# Inverter.net
KiCad netlist of a schematic drawn in Altium Designer
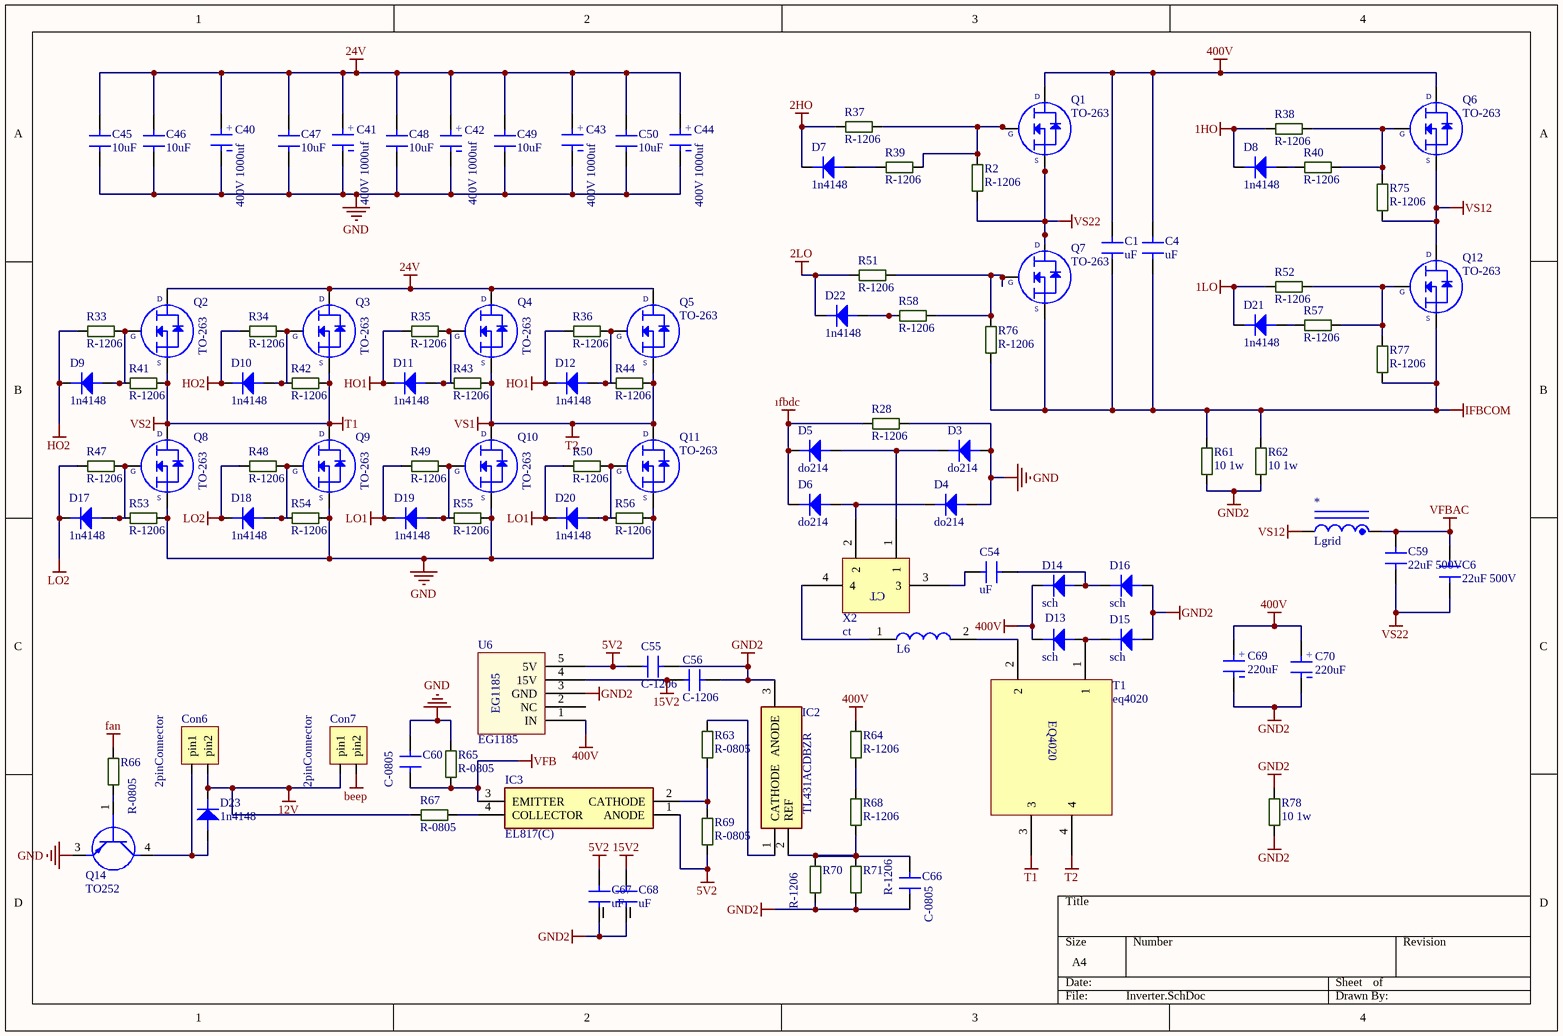
[diagram p0: Inverter.SchDoc]

(export (version "E")
  (design (tool "Eeschema 10.0.6"))
  (components
    (comp (ref "*") (value "Lgrid") (footprint "Lgrid") (libsource (lib "Schlib1") (part "Lgrid")))
    (comp (ref "C1") (value "uF") (footprint "680nF bulk") (libsource (lib "Schlib1") (part "680")))
    (comp (ref "C4") (value "uF") (footprint "680nF bulk") (libsource (lib "Schlib1") (part "680")))
    (comp (ref "C6")
      (value "22uF 500V")
      (footprint "CAP.POL 22UF 500VDC - duplicate")
      (libsource (lib "Schlib1") (part "CAP.POL 22UF 500VDC"))
    )
    (comp (ref "C40")
      (value "400V 1000uf")
      (footprint "CAP_EEETC1C331V")
      (fields
        (field (name "MANUFACTURER") "Nichicon")
        (field (name "MANUFACTURER PART NUMBER") "LKS1J472MESZ")
        (field (name "TOLERANCE") "20%")
      )
      (libsource (lib "Schlib1") (part "Aluminum Electrolytic Capacitors"))
    )
    (comp (ref "C41")
      (value "400V 1000uf")
      (footprint "CAP_EEETC1C331V")
      (fields
        (field (name "MANUFACTURER") "Nichicon")
        (field (name "MANUFACTURER PART NUMBER") "LKS1J472MESZ")
        (field (name "TOLERANCE") "20%")
      )
      (libsource (lib "Schlib1") (part "Aluminum Electrolytic Capacitors"))
    )
    (comp (ref "C42")
      (value "400V 1000uf")
      (footprint "CAP_EEETC1C331V")
      (fields
        (field (name "MANUFACTURER") "Nichicon")
        (field (name "MANUFACTURER PART NUMBER") "LKS1J472MESZ")
        (field (name "TOLERANCE") "20%")
      )
      (libsource (lib "Schlib1") (part "Aluminum Electrolytic Capacitors"))
    )
    (comp (ref "C43")
      (value "400V 1000uf")
      (footprint "CAP_EEETC1C331V")
      (fields
        (field (name "MANUFACTURER") "Nichicon")
        (field (name "MANUFACTURER PART NUMBER") "LKS1J472MESZ")
        (field (name "TOLERANCE") "20%")
      )
      (libsource (lib "Schlib1") (part "Aluminum Electrolytic Capacitors"))
    )
    (comp (ref "C44")
      (value "400V 1000uf")
      (footprint "CAP_EEETC1C331V")
      (fields
        (field (name "MANUFACTURER") "Nichicon")
        (field (name "MANUFACTURER PART NUMBER") "LKS1J472MESZ")
        (field (name "TOLERANCE") "20%")
      )
      (libsource (lib "Schlib1") (part "Aluminum Electrolytic Capacitors"))
    )
    (comp (ref "C45")
      (value "10uF")
      (footprint "C-2220R")
      (description "2220")
      (fields (field (name "ÖZDISAN PART NUMBER") " CL31B475KBHNNNE") (field (name "MANUFACTURER") "SAMSUNG"))
      (libsource (lib "Schlib1") (part "Cap2220"))
    )
    (comp (ref "C46")
      (value "10uF")
      (footprint "C-2220R")
      (description "2220")
      (fields (field (name "ÖZDISAN PART NUMBER") " CL31B475KBHNNNE") (field (name "MANUFACTURER") "SAMSUNG"))
      (libsource (lib "Schlib1") (part "Cap2220"))
    )
    (comp (ref "C47")
      (value "10uF")
      (footprint "C-2220R")
      (description "2220")
      (fields (field (name "ÖZDISAN PART NUMBER") " CL31B475KBHNNNE") (field (name "MANUFACTURER") "SAMSUNG"))
      (libsource (lib "Schlib1") (part "Cap2220"))
    )
    (comp (ref "C48")
      (value "10uF")
      (footprint "C-2220R")
      (description "2220")
      (fields (field (name "ÖZDISAN PART NUMBER") " CL31B475KBHNNNE") (field (name "MANUFACTURER") "SAMSUNG"))
      (libsource (lib "Schlib1") (part "Cap2220"))
    )
    (comp (ref "C49")
      (value "10uF")
      (footprint "C-2220R")
      (description "2220")
      (fields (field (name "ÖZDISAN PART NUMBER") " CL31B475KBHNNNE") (field (name "MANUFACTURER") "SAMSUNG"))
      (libsource (lib "Schlib1") (part "Cap2220"))
    )
    (comp (ref "C50")
      (value "10uF")
      (footprint "C-2220R")
      (description "2220")
      (fields (field (name "ÖZDISAN PART NUMBER") " CL31B475KBHNNNE") (field (name "MANUFACTURER") "SAMSUNG"))
      (libsource (lib "Schlib1") (part "Cap2220"))
    )
    (comp (ref "C54") (value "uF") (footprint "680nF bulk") (libsource (lib "Schlib1") (part "680")))
    (comp (ref "C55") (value "C-1206") (footprint "C-1206W") (libsource (lib "Schlib1") (part "C-1206")))
    (comp (ref "C56") (value "C-1206") (footprint "C-1206W") (libsource (lib "Schlib1") (part "C-1206")))
    (comp (ref "C59")
      (value "22uF 500V")
      (footprint "CAP.POL 22UF 500VDC - duplicate")
      (libsource (lib "Schlib1") (part "CAP.POL 22UF 500VDC"))
    )
    (comp (ref "C60") (value "C-0805") (footprint "C-0805W") (libsource (lib "Schlib1") (part "C-0805")))
    (comp (ref "C66") (value "C-0805") (footprint "C-0805W") (libsource (lib "Schlib1") (part "C-0805")))
    (comp (ref "C67") (value "uF") (footprint "CapSmdElc") (libsource (lib "Schlib1") (part "CAPSMDELC")))
    (comp (ref "C68") (value "uF") (footprint "CapSmdElc") (libsource (lib "Schlib1") (part "CAPSMDELC")))
    (comp (ref "C69")
      (value "220uF")
      (footprint "Koshin")
      (libsource (lib "Schlib1") (part "CAP.EL.220uF 500V"))
    )
    (comp (ref "C70")
      (value "220uF")
      (footprint "Koshin")
      (libsource (lib "Schlib1") (part "CAP.EL.220uF 500V"))
    )
    (comp (ref "Con6")
      (value "2pinConnector")
      (footprint "2pinCon")
      (libsource (lib "Schlib1") (part "2pinConnector"))
    )
    (comp (ref "Con7")
      (value "2pinConnector")
      (footprint "2pinCon")
      (libsource (lib "Schlib1") (part "2pinConnector"))
    )
    (comp (ref "D3")
      (value "do214")
      (footprint "DO-214AC")
      (description "DIODE FAST SWITCHING Single 150mA 75V SMT SOD323")
      (libsource (lib "Schlib1") (part "do214"))
    )
    (comp (ref "D4")
      (value "do214")
      (footprint "DO-214AC")
      (description "DIODE FAST SWITCHING Single 150mA 75V SMT SOD323")
      (libsource (lib "Schlib1") (part "do214"))
    )
    (comp (ref "D5")
      (value "do214")
      (footprint "DO-214AC")
      (description "DIODE FAST SWITCHING Single 150mA 75V SMT SOD323")
      (libsource (lib "Schlib1") (part "do214"))
    )
    (comp (ref "D6")
      (value "do214")
      (footprint "DO-214AC")
      (description "DIODE FAST SWITCHING Single 150mA 75V SMT SOD323")
      (libsource (lib "Schlib1") (part "do214"))
    )
    (comp (ref "D7")
      (value "1n4148")
      (footprint "SOD123")
      (description "Diode Small Signal Switching 100V 0.15A 2-Pin SOD-123 T/R")
      (fields
        (field (name "MANUFACTURER") "Vishay")
        (field (name "MANUFACTURER PART NUMBER") "1N4148W-E3-18")
      )
      (libsource (lib "Schlib1") (part "1N4148W-E3-18"))
    )
    (comp (ref "D8")
      (value "1n4148")
      (footprint "SOD123")
      (description "Diode Small Signal Switching 100V 0.15A 2-Pin SOD-123 T/R")
      (fields
        (field (name "MANUFACTURER") "Vishay")
        (field (name "MANUFACTURER PART NUMBER") "1N4148W-E3-18")
      )
      (libsource (lib "Schlib1") (part "1N4148W-E3-18"))
    )
    (comp (ref "D9")
      (value "1n4148")
      (footprint "SOD123")
      (description "Diode Small Signal Switching 100V 0.15A 2-Pin SOD-123 T/R")
      (fields
        (field (name "MANUFACTURER") "Vishay")
        (field (name "MANUFACTURER PART NUMBER") "1N4148W-E3-18")
      )
      (libsource (lib "Schlib1") (part "1N4148W-E3-18"))
    )
    (comp (ref "D10")
      (value "1n4148")
      (footprint "SOD123")
      (description "Diode Small Signal Switching 100V 0.15A 2-Pin SOD-123 T/R")
      (fields
        (field (name "MANUFACTURER") "Vishay")
        (field (name "MANUFACTURER PART NUMBER") "1N4148W-E3-18")
      )
      (libsource (lib "Schlib1") (part "1N4148W-E3-18"))
    )
    (comp (ref "D11")
      (value "1n4148")
      (footprint "SOD123")
      (description "Diode Small Signal Switching 100V 0.15A 2-Pin SOD-123 T/R")
      (fields
        (field (name "MANUFACTURER") "Vishay")
        (field (name "MANUFACTURER PART NUMBER") "1N4148W-E3-18")
      )
      (libsource (lib "Schlib1") (part "1N4148W-E3-18"))
    )
    (comp (ref "D12")
      (value "1n4148")
      (footprint "SOD123")
      (description "Diode Small Signal Switching 100V 0.15A 2-Pin SOD-123 T/R")
      (fields
        (field (name "MANUFACTURER") "Vishay")
        (field (name "MANUFACTURER PART NUMBER") "1N4148W-E3-18")
      )
      (libsource (lib "Schlib1") (part "1N4148W-E3-18"))
    )
    (comp (ref "D13")
      (value "sch")
      (footprint "DPAK_TO263 - sch")
      (description "DIODE FAST SWITCHING Single 150mA 75V SMT SOD323")
      (libsource (lib "Schlib1") (part "sch"))
    )
    (comp (ref "D14")
      (value "sch")
      (footprint "DPAK_TO263 - sch")
      (description "DIODE FAST SWITCHING Single 150mA 75V SMT SOD323")
      (libsource (lib "Schlib1") (part "sch"))
    )
    (comp (ref "D15")
      (value "sch")
      (footprint "DPAK_TO263 - sch")
      (description "DIODE FAST SWITCHING Single 150mA 75V SMT SOD323")
      (libsource (lib "Schlib1") (part "sch"))
    )
    (comp (ref "D16")
      (value "sch")
      (footprint "DPAK_TO263 - sch")
      (description "DIODE FAST SWITCHING Single 150mA 75V SMT SOD323")
      (libsource (lib "Schlib1") (part "sch"))
    )
    (comp (ref "D17")
      (value "1n4148")
      (footprint "SOD123")
      (description "Diode Small Signal Switching 100V 0.15A 2-Pin SOD-123 T/R")
      (fields
        (field (name "MANUFACTURER") "Vishay")
        (field (name "MANUFACTURER PART NUMBER") "1N4148W-E3-18")
      )
      (libsource (lib "Schlib1") (part "1N4148W-E3-18"))
    )
    (comp (ref "D18")
      (value "1n4148")
      (footprint "SOD123")
      (description "Diode Small Signal Switching 100V 0.15A 2-Pin SOD-123 T/R")
      (fields
        (field (name "MANUFACTURER") "Vishay")
        (field (name "MANUFACTURER PART NUMBER") "1N4148W-E3-18")
      )
      (libsource (lib "Schlib1") (part "1N4148W-E3-18"))
    )
    (comp (ref "D19")
      (value "1n4148")
      (footprint "SOD123")
      (description "Diode Small Signal Switching 100V 0.15A 2-Pin SOD-123 T/R")
      (fields
        (field (name "MANUFACTURER") "Vishay")
        (field (name "MANUFACTURER PART NUMBER") "1N4148W-E3-18")
      )
      (libsource (lib "Schlib1") (part "1N4148W-E3-18"))
    )
    (comp (ref "D20")
      (value "1n4148")
      (footprint "SOD123")
      (description "Diode Small Signal Switching 100V 0.15A 2-Pin SOD-123 T/R")
      (fields
        (field (name "MANUFACTURER") "Vishay")
        (field (name "MANUFACTURER PART NUMBER") "1N4148W-E3-18")
      )
      (libsource (lib "Schlib1") (part "1N4148W-E3-18"))
    )
    (comp (ref "D21")
      (value "1n4148")
      (footprint "SOD123")
      (description "Diode Small Signal Switching 100V 0.15A 2-Pin SOD-123 T/R")
      (fields
        (field (name "MANUFACTURER") "Vishay")
        (field (name "MANUFACTURER PART NUMBER") "1N4148W-E3-18")
      )
      (libsource (lib "Schlib1") (part "1N4148W-E3-18"))
    )
    (comp (ref "D22")
      (value "1n4148")
      (footprint "SOD123")
      (description "Diode Small Signal Switching 100V 0.15A 2-Pin SOD-123 T/R")
      (fields
        (field (name "MANUFACTURER") "Vishay")
        (field (name "MANUFACTURER PART NUMBER") "1N4148W-E3-18")
      )
      (libsource (lib "Schlib1") (part "1N4148W-E3-18"))
    )
    (comp (ref "D23")
      (value "1n4148")
      (footprint "SOD123")
      (description "Diode Small Signal Switching 100V 0.15A 2-Pin SOD-123 T/R")
      (fields
        (field (name "MANUFACTURER") "Vishay")
        (field (name "MANUFACTURER PART NUMBER") "1N4148W-E3-18")
      )
      (libsource (lib "Schlib1") (part "1N4148W-E3-18"))
    )
    (comp (ref "IC2")
      (value "TL431ACDBZR")
      (footprint "SamacSys:SOT95P237X112-3N")
      (description "Integrated Circuit")
      (fields (field (name "MOUSER PART NUMBER") "595-TL431ACDBZR"))
      (libsource (lib "*") (part "TL431ACDBZR"))
    )
    (comp (ref "IC3")
      (value "EL817(C)")
      (footprint "DIP762W60P254L458H480Q4N")
      (description "Integrated Circuit")
      (fields (field (name "MOUSER PART NUMBER") "638-EL817C"))
      (libsource (lib "Schlib1") (part "EL817(C)"))
    )
    (comp (ref "L6")
      (value "inducter_SMPI06050")
      (footprint "inductor")
      (libsource (lib "Schlib1") (part "inducter_SMPI06050"))
    )
    (comp (ref "Q1") (value "TO-263") (footprint "DPAK_TO263") (libsource (lib "Schlib1") (part "TO-263_1")))
    (comp (ref "Q2") (value "TO-263") (footprint "DPAK_TO263") (libsource (lib "Schlib1") (part "TO-263_1")))
    (comp (ref "Q3") (value "TO-263") (footprint "DPAK_TO263") (libsource (lib "Schlib1") (part "TO-263_1")))
    (comp (ref "Q4") (value "TO-263") (footprint "DPAK_TO263") (libsource (lib "Schlib1") (part "TO-263_1")))
    (comp (ref "Q5") (value "TO-263") (footprint "DPAK_TO263") (libsource (lib "Schlib1") (part "TO-263_1")))
    (comp (ref "Q6") (value "TO-263") (footprint "DPAK_TO263") (libsource (lib "Schlib1") (part "TO-263_1")))
    (comp (ref "Q7") (value "TO-263") (footprint "DPAK_TO263") (libsource (lib "Schlib1") (part "TO-263_1")))
    (comp (ref "Q8") (value "TO-263") (footprint "DPAK_TO263") (libsource (lib "Schlib1") (part "TO-263_1")))
    (comp (ref "Q9") (value "TO-263") (footprint "DPAK_TO263") (libsource (lib "Schlib1") (part "TO-263_1")))
    (comp (ref "Q10") (value "TO-263") (footprint "DPAK_TO263") (libsource (lib "Schlib1") (part "TO-263_1")))
    (comp (ref "Q11") (value "TO-263") (footprint "DPAK_TO263") (libsource (lib "Schlib1") (part "TO-263_1")))
    (comp (ref "Q12") (value "TO-263") (footprint "DPAK_TO263") (libsource (lib "Schlib1") (part "TO-263_1")))
    (comp (ref "Q14") (value "TO252") (footprint "D-PAK_TO252AA") (libsource (lib "Schlib1") (part "TO252")))
    (comp (ref "R2") (value "R-1206") (footprint "R-1206W") (libsource (lib "Schlib1") (part "R-1206")))
    (comp (ref "R28") (value "R-1206") (footprint "R-1206W") (libsource (lib "Schlib1") (part "R-1206")))
    (comp (ref "R33") (value "R-1206") (footprint "R-1206W") (libsource (lib "Schlib1") (part "R-1206")))
    (comp (ref "R34") (value "R-1206") (footprint "R-1206W") (libsource (lib "Schlib1") (part "R-1206")))
    (comp (ref "R35") (value "R-1206") (footprint "R-1206W") (libsource (lib "Schlib1") (part "R-1206")))
    (comp (ref "R36") (value "R-1206") (footprint "R-1206W") (libsource (lib "Schlib1") (part "R-1206")))
    (comp (ref "R37") (value "R-1206") (footprint "R-1206W") (libsource (lib "Schlib1") (part "R-1206")))
    (comp (ref "R38") (value "R-1206") (footprint "R-1206W") (libsource (lib "Schlib1") (part "R-1206")))
    (comp (ref "R39") (value "R-1206") (footprint "R-1206W") (libsource (lib "Schlib1") (part "R-1206")))
    (comp (ref "R40") (value "R-1206") (footprint "R-1206W") (libsource (lib "Schlib1") (part "R-1206")))
    (comp (ref "R41") (value "R-1206") (footprint "R-1206W") (libsource (lib "Schlib1") (part "R-1206")))
    (comp (ref "R42") (value "R-1206") (footprint "R-1206W") (libsource (lib "Schlib1") (part "R-1206")))
    (comp (ref "R43") (value "R-1206") (footprint "R-1206W") (libsource (lib "Schlib1") (part "R-1206")))
    (comp (ref "R44") (value "R-1206") (footprint "R-1206W") (libsource (lib "Schlib1") (part "R-1206")))
    (comp (ref "R47") (value "R-1206") (footprint "R-1206W") (libsource (lib "Schlib1") (part "R-1206")))
    (comp (ref "R48") (value "R-1206") (footprint "R-1206W") (libsource (lib "Schlib1") (part "R-1206")))
    (comp (ref "R49") (value "R-1206") (footprint "R-1206W") (libsource (lib "Schlib1") (part "R-1206")))
    (comp (ref "R50") (value "R-1206") (footprint "R-1206W") (libsource (lib "Schlib1") (part "R-1206")))
    (comp (ref "R51") (value "R-1206") (footprint "R-1206W") (libsource (lib "Schlib1") (part "R-1206")))
    (comp (ref "R52") (value "R-1206") (footprint "R-1206W") (libsource (lib "Schlib1") (part "R-1206")))
    (comp (ref "R53") (value "R-1206") (footprint "R-1206W") (libsource (lib "Schlib1") (part "R-1206")))
    (comp (ref "R54") (value "R-1206") (footprint "R-1206W") (libsource (lib "Schlib1") (part "R-1206")))
    (comp (ref "R55") (value "R-1206") (footprint "R-1206W") (libsource (lib "Schlib1") (part "R-1206")))
    (comp (ref "R56") (value "R-1206") (footprint "R-1206W") (libsource (lib "Schlib1") (part "R-1206")))
    (comp (ref "R57") (value "R-1206") (footprint "R-1206W") (libsource (lib "Schlib1") (part "R-1206")))
    (comp (ref "R58") (value "R-1206") (footprint "R-1206W") (libsource (lib "Schlib1") (part "R-1206")))
    (comp (ref "R61") (value "10 1w") (footprint "R-2512W") (libsource (lib "Schlib1") (part "R-2512")))
    (comp (ref "R62") (value "10 1w") (footprint "R-2512W") (libsource (lib "Schlib1") (part "R-2512")))
    (comp (ref "R63") (value "R-0805") (footprint "R-0805W") (libsource (lib "Schlib1") (part "R-0805")))
    (comp (ref "R64") (value "R-1206") (footprint "R-1206W") (libsource (lib "Schlib1") (part "R-1206")))
    (comp (ref "R65") (value "R-0805") (footprint "R-0805W") (libsource (lib "Schlib1") (part "R-0805")))
    (comp (ref "R66") (value "R-0805") (footprint "R-0805W") (libsource (lib "Schlib1") (part "R-0805")))
    (comp (ref "R67") (value "R-0805") (footprint "R-0805W") (libsource (lib "Schlib1") (part "R-0805")))
    (comp (ref "R68") (value "R-1206") (footprint "R-1206W") (libsource (lib "Schlib1") (part "R-1206")))
    (comp (ref "R69") (value "R-0805") (footprint "R-0805W") (libsource (lib "Schlib1") (part "R-0805")))
    (comp (ref "R70") (value "R-1206") (footprint "R-1206W") (libsource (lib "Schlib1") (part "R-1206")))
    (comp (ref "R71") (value "R-1206") (footprint "R-1206W") (libsource (lib "Schlib1") (part "R-1206")))
    (comp (ref "R75") (value "R-1206") (footprint "R-1206W") (libsource (lib "Schlib1") (part "R-1206")))
    (comp (ref "R76") (value "R-1206") (footprint "R-1206W") (libsource (lib "Schlib1") (part "R-1206")))
    (comp (ref "R77") (value "R-1206") (footprint "R-1206W") (libsource (lib "Schlib1") (part "R-1206")))
    (comp (ref "R78") (value "10 1w") (footprint "R-2512W") (libsource (lib "Schlib1") (part "R-2512")))
    (comp (ref "T1") (value "eq4020") (footprint "eq4020") (libsource (lib "Schlib1") (part "eq4020")))
    (comp (ref "U6") (value "EG1185") (footprint "EG1185") (libsource (lib "Schlib1") (part "eg1185")))
    (comp (ref "X2") (value "ct") (footprint "ct") (libsource (lib "Schlib1") (part "ct")))
  )
  (nets
    (net (code "1") (name "1HO") (class "Default")
      (node (ref "D8") (pin "k") (pinfunction "k_k") (pintype "passive"))
      (node (ref "R38") (pin "1") (pinfunction "1_1") (pintype "passive"))
    )
    (net (code "2") (name "1LO") (class "Default")
      (node (ref "D21") (pin "k") (pinfunction "k_k") (pintype "passive"))
      (node (ref "R52") (pin "1") (pinfunction "1_1") (pintype "passive"))
    )
    (net (code "3") (name "2HO") (class "Default")
      (node (ref "D7") (pin "k") (pinfunction "k_k") (pintype "passive"))
      (node (ref "R37") (pin "1") (pinfunction "1_1") (pintype "passive"))
    )
    (net (code "4") (name "2LO") (class "Default")
      (node (ref "D22") (pin "k") (pinfunction "k_k") (pintype "passive"))
      (node (ref "R51") (pin "1") (pinfunction "1_1") (pintype "passive"))
    )
    (net (code "5") (name "5V2") (class "Default")
      (node (ref "C55") (pin "1") (pinfunction "1_1") (pintype "passive"))
      (node (ref "C67") (pin "1") (pinfunction "1_1") (pintype "passive"))
      (node (ref "IC3") (pin "1") (pinfunction "ANODE_1") (pintype "passive"))
      (node (ref "R69") (pin "1") (pinfunction "1_1") (pintype "passive"))
      (node (ref "U6") (pin "5") (pinfunction "5V_5") (pintype "passive"))
    )
    (net (code "6") (name "12V") (class "Default")
      (node (ref "Con6") (pin "2") (pinfunction "pin2_2") (pintype "passive"))
      (node (ref "Con7") (pin "1") (pinfunction "pin1_1") (pintype "passive"))
      (node (ref "D23") (pin "k") (pinfunction "k_k") (pintype "passive"))
      (node (ref "R67") (pin "1") (pinfunction "1_1") (pintype "passive"))
    )
    (net (code "7") (name "15V2") (class "Default")
      (node (ref "C56") (pin "1") (pinfunction "1_1") (pintype "passive"))
      (node (ref "C68") (pin "1") (pinfunction "1_1") (pintype "passive"))
      (node (ref "U6") (pin "4") (pinfunction "15V_4") (pintype "passive"))
    )
    (net (code "8") (name "24V") (class "Default")
      (node (ref "C40") (pin "1") (pinfunction "1_1") (pintype "passive"))
      (node (ref "C41") (pin "1") (pinfunction "1_1") (pintype "passive"))
      (node (ref "C42") (pin "1") (pinfunction "1_1") (pintype "passive"))
      (node (ref "C43") (pin "1") (pinfunction "1_1") (pintype "passive"))
      (node (ref "C44") (pin "1") (pinfunction "1_1") (pintype "passive"))
      (node (ref "C45") (pin "1") (pinfunction "1_1") (pintype "passive"))
      (node (ref "C46") (pin "1") (pinfunction "1_1") (pintype "passive"))
      (node (ref "C47") (pin "1") (pinfunction "1_1") (pintype "passive"))
      (node (ref "C48") (pin "1") (pinfunction "1_1") (pintype "passive"))
      (node (ref "C49") (pin "1") (pinfunction "1_1") (pintype "passive"))
      (node (ref "C50") (pin "1") (pinfunction "1_1") (pintype "passive"))
      (node (ref "Q2") (pin "3") (pinfunction "3_3") (pintype "passive"))
      (node (ref "Q3") (pin "3") (pinfunction "3_3") (pintype "passive"))
      (node (ref "Q4") (pin "3") (pinfunction "3_3") (pintype "passive"))
      (node (ref "Q5") (pin "3") (pinfunction "3_3") (pintype "passive"))
    )
    (net (code "9") (name "400V") (class "Default")
      (node (ref "C1") (pin "2") (pinfunction "2_2") (pintype "passive"))
      (node (ref "C4") (pin "2") (pinfunction "2_2") (pintype "passive"))
      (node (ref "C69") (pin "2") (pinfunction "2_2") (pintype "passive"))
      (node (ref "C70") (pin "2") (pinfunction "2_2") (pintype "passive"))
      (node (ref "D13") (pin "1") (pinfunction "1_1") (pintype "passive"))
      (node (ref "D14") (pin "1") (pinfunction "1_1") (pintype "passive"))
      (node (ref "Q1") (pin "3") (pinfunction "3_3") (pintype "passive"))
      (node (ref "Q6") (pin "3") (pinfunction "3_3") (pintype "passive"))
      (node (ref "R64") (pin "2") (pinfunction "2_2") (pintype "passive"))
      (node (ref "U6") (pin "1") (pinfunction "IN_1") (pintype "passive"))
    )
    (net (code "10") (name "GND") (class "Default")
      (node (ref "C40") (pin "2") (pinfunction "2_2") (pintype "passive"))
      (node (ref "C41") (pin "2") (pinfunction "2_2") (pintype "passive"))
      (node (ref "C42") (pin "2") (pinfunction "2_2") (pintype "passive"))
      (node (ref "C43") (pin "2") (pinfunction "2_2") (pintype "passive"))
      (node (ref "C44") (pin "2") (pinfunction "2_2") (pintype "passive"))
      (node (ref "C45") (pin "2") (pinfunction "2_2") (pintype "passive"))
      (node (ref "C46") (pin "2") (pinfunction "2_2") (pintype "passive"))
      (node (ref "C47") (pin "2") (pinfunction "2_2") (pintype "passive"))
      (node (ref "C48") (pin "2") (pinfunction "2_2") (pintype "passive"))
      (node (ref "C49") (pin "2") (pinfunction "2_2") (pintype "passive"))
      (node (ref "C50") (pin "2") (pinfunction "2_2") (pintype "passive"))
      (node (ref "C60") (pin "2") (pinfunction "2_2") (pintype "passive"))
      (node (ref "D3") (pin "a") (pinfunction "a_a") (pintype "passive"))
      (node (ref "D4") (pin "a") (pinfunction "a_a") (pintype "passive"))
      (node (ref "Q10") (pin "2") (pinfunction "2_2") (pintype "passive"))
      (node (ref "Q11") (pin "2") (pinfunction "2_2") (pintype "passive"))
      (node (ref "Q14") (pin "3") (pinfunction "E_3") (pintype "passive"))
      (node (ref "Q8") (pin "2") (pinfunction "2_2") (pintype "passive"))
      (node (ref "Q9") (pin "2") (pinfunction "2_2") (pintype "passive"))
      (node (ref "R28") (pin "2") (pinfunction "2_2") (pintype "passive"))
      (node (ref "R53") (pin "2") (pinfunction "2_2") (pintype "passive"))
      (node (ref "R54") (pin "2") (pinfunction "2_2") (pintype "passive"))
      (node (ref "R55") (pin "2") (pinfunction "2_2") (pintype "passive"))
      (node (ref "R56") (pin "2") (pinfunction "2_2") (pintype "passive"))
      (node (ref "R65") (pin "2") (pinfunction "2_2") (pintype "passive"))
    )
    (net (code "11") (name "GND2") (class "Default")
      (node (ref "C55") (pin "2") (pinfunction "2_2") (pintype "passive"))
      (node (ref "C56") (pin "2") (pinfunction "2_2") (pintype "passive"))
      (node (ref "C66") (pin "1") (pinfunction "1_1") (pintype "passive"))
      (node (ref "C67") (pin "2") (pinfunction "2_2") (pintype "passive"))
      (node (ref "C68") (pin "2") (pinfunction "2_2") (pintype "passive"))
      (node (ref "C69") (pin "1") (pinfunction "1_1") (pintype "passive"))
      (node (ref "C70") (pin "1") (pinfunction "1_1") (pintype "passive"))
      (node (ref "D15") (pin "2") (pinfunction "2_2") (pintype "passive"))
      (node (ref "D16") (pin "2") (pinfunction "2_2") (pintype "passive"))
      (node (ref "IC2") (pin "3") (pinfunction "ANODE_3") (pintype "passive"))
      (node (ref "R61") (pin "1") (pinfunction "1_1") (pintype "passive"))
      (node (ref "R62") (pin "1") (pinfunction "1_1") (pintype "passive"))
      (node (ref "R70") (pin "1") (pinfunction "1_1") (pintype "passive"))
      (node (ref "R71") (pin "1") (pinfunction "1_1") (pintype "passive"))
      (node (ref "R78") (pin "1") (pinfunction "1_1") (pintype "passive"))
      (node (ref "R78") (pin "2") (pinfunction "2_2") (pintype "passive"))
      (node (ref "U6") (pin "3") (pinfunction "GND_3") (pintype "passive"))
    )
    (net (code "12") (name "HO1") (class "Default")
      (node (ref "D11") (pin "k") (pinfunction "k_k") (pintype "passive"))
      (node (ref "D12") (pin "k") (pinfunction "k_k") (pintype "passive"))
      (node (ref "R35") (pin "1") (pinfunction "1_1") (pintype "passive"))
      (node (ref "R36") (pin "1") (pinfunction "1_1") (pintype "passive"))
    )
    (net (code "13") (name "HO2") (class "Default")
      (node (ref "D10") (pin "k") (pinfunction "k_k") (pintype "passive"))
      (node (ref "D9") (pin "k") (pinfunction "k_k") (pintype "passive"))
      (node (ref "R33") (pin "1") (pinfunction "1_1") (pintype "passive"))
      (node (ref "R34") (pin "1") (pinfunction "1_1") (pintype "passive"))
    )
    (net (code "14") (name "IFBCOM") (class "Default")
      (node (ref "C1") (pin "1") (pinfunction "1_1") (pintype "passive"))
      (node (ref "C4") (pin "1") (pinfunction "1_1") (pintype "passive"))
      (node (ref "Q12") (pin "2") (pinfunction "2_2") (pintype "passive"))
      (node (ref "Q7") (pin "2") (pinfunction "2_2") (pintype "passive"))
      (node (ref "R61") (pin "2") (pinfunction "2_2") (pintype "passive"))
      (node (ref "R62") (pin "2") (pinfunction "2_2") (pintype "passive"))
      (node (ref "R76") (pin "1") (pinfunction "1_1") (pintype "passive"))
      (node (ref "R77") (pin "2") (pinfunction "2_2") (pintype "passive"))
    )
    (net (code "15") (name "LO1") (class "Default")
      (node (ref "D19") (pin "k") (pinfunction "k_k") (pintype "passive"))
      (node (ref "D20") (pin "k") (pinfunction "k_k") (pintype "passive"))
      (node (ref "R49") (pin "1") (pinfunction "1_1") (pintype "passive"))
      (node (ref "R50") (pin "1") (pinfunction "1_1") (pintype "passive"))
    )
    (net (code "16") (name "LO2") (class "Default")
      (node (ref "D17") (pin "k") (pinfunction "k_k") (pintype "passive"))
      (node (ref "D18") (pin "k") (pinfunction "k_k") (pintype "passive"))
      (node (ref "R47") (pin "1") (pinfunction "1_1") (pintype "passive"))
      (node (ref "R48") (pin "1") (pinfunction "1_1") (pintype "passive"))
    )
    (net (code "17") (name "Net-(C54-Pad1)") (class "Default")
      (node (ref "C54") (pin "1") (pinfunction "1_1") (pintype "passive"))
      (node (ref "X2") (pin "3") (pinfunction "3_3") (pintype "passive"))
    )
    (net (code "18") (name "Net-(C54-Pad2)") (class "Default")
      (node (ref "C54") (pin "2") (pinfunction "2_2") (pintype "passive"))
      (node (ref "D14") (pin "2") (pinfunction "2_2") (pintype "passive"))
      (node (ref "D16") (pin "1") (pinfunction "1_1") (pintype "passive"))
    )
    (net (code "19") (name "Net-(Con6-pin1)") (class "Default")
      (node (ref "Con6") (pin "1") (pinfunction "pin1_1") (pintype "passive"))
      (node (ref "D23") (pin "a") (pinfunction "a_a") (pintype "passive"))
      (node (ref "Q14") (pin "4") (pinfunction "C_4") (pintype "passive"))
    )
    (net (code "20") (name "Net-(D3-Padk)") (class "Default")
      (node (ref "D3") (pin "k") (pinfunction "k_k") (pintype "passive"))
      (node (ref "D5") (pin "a") (pinfunction "a_a") (pintype "passive"))
      (node (ref "X2") (pin "1") (pinfunction "1_1") (pintype "passive"))
    )
    (net (code "21") (name "Net-(D4-Padk)") (class "Default")
      (node (ref "D4") (pin "k") (pinfunction "k_k") (pintype "passive"))
      (node (ref "D6") (pin "a") (pinfunction "a_a") (pintype "passive"))
      (node (ref "X2") (pin "2") (pinfunction "2_2") (pintype "passive"))
    )
    (net (code "22") (name "Net-(D7-Pada)") (class "Default")
      (node (ref "D7") (pin "a") (pinfunction "a_a") (pintype "passive"))
      (node (ref "R39") (pin "1") (pinfunction "1_1") (pintype "passive"))
    )
    (net (code "23") (name "Net-(D8-Pada)") (class "Default")
      (node (ref "D8") (pin "a") (pinfunction "a_a") (pintype "passive"))
      (node (ref "R40") (pin "1") (pinfunction "1_1") (pintype "passive"))
    )
    (net (code "24") (name "Net-(D9-Pada)") (class "Default")
      (node (ref "D9") (pin "a") (pinfunction "a_a") (pintype "passive"))
      (node (ref "Q2") (pin "1") (pinfunction "1_1") (pintype "passive"))
      (node (ref "R33") (pin "2") (pinfunction "2_2") (pintype "passive"))
      (node (ref "R41") (pin "1") (pinfunction "1_1") (pintype "passive"))
    )
    (net (code "25") (name "Net-(D10-Pada)") (class "Default")
      (node (ref "D10") (pin "a") (pinfunction "a_a") (pintype "passive"))
      (node (ref "Q3") (pin "1") (pinfunction "1_1") (pintype "passive"))
      (node (ref "R34") (pin "2") (pinfunction "2_2") (pintype "passive"))
      (node (ref "R42") (pin "1") (pinfunction "1_1") (pintype "passive"))
    )
    (net (code "26") (name "Net-(D11-Pada)") (class "Default")
      (node (ref "D11") (pin "a") (pinfunction "a_a") (pintype "passive"))
      (node (ref "Q4") (pin "1") (pinfunction "1_1") (pintype "passive"))
      (node (ref "R35") (pin "2") (pinfunction "2_2") (pintype "passive"))
      (node (ref "R43") (pin "1") (pinfunction "1_1") (pintype "passive"))
    )
    (net (code "27") (name "Net-(D12-Pada)") (class "Default")
      (node (ref "D12") (pin "a") (pinfunction "a_a") (pintype "passive"))
      (node (ref "Q5") (pin "1") (pinfunction "1_1") (pintype "passive"))
      (node (ref "R36") (pin "2") (pinfunction "2_2") (pintype "passive"))
      (node (ref "R44") (pin "1") (pinfunction "1_1") (pintype "passive"))
    )
    (net (code "28") (name "Net-(D13-Pad2)") (class "Default")
      (node (ref "D13") (pin "2") (pinfunction "2_2") (pintype "passive"))
      (node (ref "D15") (pin "1") (pinfunction "1_1") (pintype "passive"))
      (node (ref "T1") (pin "1") (pinfunction "1_1") (pintype "passive"))
    )
    (net (code "29") (name "Net-(D17-Pada)") (class "Default")
      (node (ref "D17") (pin "a") (pinfunction "a_a") (pintype "passive"))
      (node (ref "Q8") (pin "1") (pinfunction "1_1") (pintype "passive"))
      (node (ref "R47") (pin "2") (pinfunction "2_2") (pintype "passive"))
      (node (ref "R53") (pin "1") (pinfunction "1_1") (pintype "passive"))
    )
    (net (code "30") (name "Net-(D18-Pada)") (class "Default")
      (node (ref "D18") (pin "a") (pinfunction "a_a") (pintype "passive"))
      (node (ref "Q9") (pin "1") (pinfunction "1_1") (pintype "passive"))
      (node (ref "R48") (pin "2") (pinfunction "2_2") (pintype "passive"))
      (node (ref "R54") (pin "1") (pinfunction "1_1") (pintype "passive"))
    )
    (net (code "31") (name "Net-(D19-Pada)") (class "Default")
      (node (ref "D19") (pin "a") (pinfunction "a_a") (pintype "passive"))
      (node (ref "Q10") (pin "1") (pinfunction "1_1") (pintype "passive"))
      (node (ref "R49") (pin "2") (pinfunction "2_2") (pintype "passive"))
      (node (ref "R55") (pin "1") (pinfunction "1_1") (pintype "passive"))
    )
    (net (code "32") (name "Net-(D20-Pada)") (class "Default")
      (node (ref "D20") (pin "a") (pinfunction "a_a") (pintype "passive"))
      (node (ref "Q11") (pin "1") (pinfunction "1_1") (pintype "passive"))
      (node (ref "R50") (pin "2") (pinfunction "2_2") (pintype "passive"))
      (node (ref "R56") (pin "1") (pinfunction "1_1") (pintype "passive"))
    )
    (net (code "33") (name "Net-(D21-Pada)") (class "Default")
      (node (ref "D21") (pin "a") (pinfunction "a_a") (pintype "passive"))
      (node (ref "R57") (pin "1") (pinfunction "1_1") (pintype "passive"))
    )
    (net (code "34") (name "Net-(D22-Pada)") (class "Default")
      (node (ref "D22") (pin "a") (pinfunction "a_a") (pintype "passive"))
      (node (ref "R58") (pin "1") (pinfunction "1_1") (pintype "passive"))
    )
    (net (code "35") (name "Net-(IC2-CATHODE)") (class "Default")
      (node (ref "IC2") (pin "1") (pinfunction "CATHODE_1") (pintype "passive"))
      (node (ref "R63") (pin "1") (pinfunction "1_1") (pintype "passive"))
    )
    (net (code "36") (name "Net-(IC2-REF)") (class "Default")
      (node (ref "C66") (pin "2") (pinfunction "2_2") (pintype "passive"))
      (node (ref "IC2") (pin "2") (pinfunction "REF_2") (pintype "passive"))
      (node (ref "R68") (pin "1") (pinfunction "1_1") (pintype "passive"))
      (node (ref "R70") (pin "2") (pinfunction "2_2") (pintype "passive"))
      (node (ref "R71") (pin "2") (pinfunction "2_2") (pintype "passive"))
    )
    (net (code "37") (name "Net-(IC3-CATHODE)") (class "Default")
      (node (ref "IC3") (pin "2") (pinfunction "CATHODE_2") (pintype "passive"))
      (node (ref "R63") (pin "2") (pinfunction "2_2") (pintype "passive"))
      (node (ref "R69") (pin "2") (pinfunction "2_2") (pintype "passive"))
    )
    (net (code "38") (name "Net-(IC3-COLLECTOR)") (class "Default")
      (node (ref "IC3") (pin "4") (pinfunction "COLLECTOR_4") (pintype "passive"))
      (node (ref "R67") (pin "2") (pinfunction "2_2") (pintype "passive"))
    )
    (net (code "39") (name "Net-(L6-Pad1)") (class "Default")
      (node (ref "L6") (pin "1") (pinfunction "1_1") (pintype "passive"))
      (node (ref "X2") (pin "4") (pinfunction "4_4") (pintype "passive"))
    )
    (net (code "40") (name "Net-(L6-Pad2)") (class "Default")
      (node (ref "L6") (pin "2") (pinfunction "2_2") (pintype "passive"))
      (node (ref "T1") (pin "2") (pinfunction "2_2") (pintype "passive"))
    )
    (net (code "41") (name "Net-(Q1-Pad1)") (class "Default")
      (node (ref "Q1") (pin "1") (pinfunction "1_1") (pintype "passive"))
      (node (ref "R2") (pin "2") (pinfunction "2_2") (pintype "passive"))
      (node (ref "R37") (pin "2") (pinfunction "2_2") (pintype "passive"))
      (node (ref "R39") (pin "2") (pinfunction "2_2") (pintype "passive"))
    )
    (net (code "42") (name "Net-(Q6-Pad1)") (class "Default")
      (node (ref "Q6") (pin "1") (pinfunction "1_1") (pintype "passive"))
      (node (ref "R38") (pin "2") (pinfunction "2_2") (pintype "passive"))
      (node (ref "R40") (pin "2") (pinfunction "2_2") (pintype "passive"))
      (node (ref "R75") (pin "1") (pinfunction "1_1") (pintype "passive"))
    )
    (net (code "43") (name "Net-(Q7-Pad1)") (class "Default")
      (node (ref "Q7") (pin "1") (pinfunction "1_1") (pintype "passive"))
      (node (ref "R51") (pin "2") (pinfunction "2_2") (pintype "passive"))
      (node (ref "R58") (pin "2") (pinfunction "2_2") (pintype "passive"))
      (node (ref "R76") (pin "2") (pinfunction "2_2") (pintype "passive"))
    )
    (net (code "44") (name "Net-(Q12-Pad1)") (class "Default")
      (node (ref "Q12") (pin "1") (pinfunction "1_1") (pintype "passive"))
      (node (ref "R52") (pin "2") (pinfunction "2_2") (pintype "passive"))
      (node (ref "R57") (pin "2") (pinfunction "2_2") (pintype "passive"))
      (node (ref "R77") (pin "1") (pinfunction "1_1") (pintype "passive"))
    )
    (net (code "45") (name "Net-(Q14-B)") (class "Default")
      (node (ref "Q14") (pin "1") (pinfunction "B_1") (pintype "passive"))
      (node (ref "R66") (pin "2") (pinfunction "2_2") (pintype "passive"))
    )
    (net (code "46") (name "Net-(R64-Pad1)") (class "Default")
      (node (ref "R64") (pin "1") (pinfunction "1_1") (pintype "passive"))
      (node (ref "R68") (pin "2") (pinfunction "2_2") (pintype "passive"))
    )
    (net (code "47") (name "T1") (class "Default")
      (node (ref "Q2") (pin "2") (pinfunction "2_2") (pintype "passive"))
      (node (ref "Q3") (pin "2") (pinfunction "2_2") (pintype "passive"))
      (node (ref "Q8") (pin "3") (pinfunction "3_3") (pintype "passive"))
      (node (ref "Q9") (pin "3") (pinfunction "3_3") (pintype "passive"))
      (node (ref "R41") (pin "2") (pinfunction "2_2") (pintype "passive"))
      (node (ref "R42") (pin "2") (pinfunction "2_2") (pintype "passive"))
      (node (ref "T1") (pin "3") (pinfunction "3_3") (pintype "passive"))
    )
    (net (code "48") (name "T2") (class "Default")
      (node (ref "Q10") (pin "3") (pinfunction "3_3") (pintype "passive"))
      (node (ref "Q11") (pin "3") (pinfunction "3_3") (pintype "passive"))
      (node (ref "Q4") (pin "2") (pinfunction "2_2") (pintype "passive"))
      (node (ref "Q5") (pin "2") (pinfunction "2_2") (pintype "passive"))
      (node (ref "R43") (pin "2") (pinfunction "2_2") (pintype "passive"))
      (node (ref "R44") (pin "2") (pinfunction "2_2") (pintype "passive"))
      (node (ref "T1") (pin "4") (pinfunction "4_4") (pintype "passive"))
    )
    (net (code "49") (name "VFB") (class "Default")
      (node (ref "C60") (pin "1") (pinfunction "1_1") (pintype "passive"))
      (node (ref "IC3") (pin "3") (pinfunction "EMITTER_3") (pintype "passive"))
      (node (ref "R65") (pin "1") (pinfunction "1_1") (pintype "passive"))
    )
    (net (code "50") (name "VFBAC") (class "Default")
      (node (ref "*") (pin "1") (pinfunction "1_1") (pintype "passive"))
      (node (ref "C59") (pin "2") (pinfunction "2_2") (pintype "passive"))
      (node (ref "C6") (pin "2") (pinfunction "2_2") (pintype "passive"))
    )
    (net (code "51") (name "VS12") (class "Default")
      (node (ref "*") (pin "2") (pinfunction "2_2") (pintype "passive"))
      (node (ref "Q12") (pin "3") (pinfunction "3_3") (pintype "passive"))
      (node (ref "Q6") (pin "2") (pinfunction "2_2") (pintype "passive"))
      (node (ref "R75") (pin "2") (pinfunction "2_2") (pintype "passive"))
    )
    (net (code "52") (name "VS22") (class "Default")
      (node (ref "C59") (pin "1") (pinfunction "1_1") (pintype "passive"))
      (node (ref "C6") (pin "1") (pinfunction "1_1") (pintype "passive"))
      (node (ref "Q1") (pin "2") (pinfunction "2_2") (pintype "passive"))
      (node (ref "Q7") (pin "3") (pinfunction "3_3") (pintype "passive"))
      (node (ref "R2") (pin "1") (pinfunction "1_1") (pintype "passive"))
    )
    (net (code "53") (name "beep") (class "Default")
      (node (ref "Con7") (pin "2") (pinfunction "pin2_2") (pintype "passive"))
    )
    (net (code "54") (name "fan") (class "Default")
      (node (ref "R66") (pin "1") (pinfunction "1_1") (pintype "passive"))
    )
    (net (code "55") (name "unconnected-(U6-NC-Pad2)") (class "Default")
      (node (ref "U6") (pin "2") (pinfunction "NC_2") (pintype "passive"))
    )
    (net (code "56") (name "ıfbdc") (class "Default")
      (node (ref "D5") (pin "k") (pinfunction "k_k") (pintype "passive"))
      (node (ref "D6") (pin "k") (pinfunction "k_k") (pintype "passive"))
      (node (ref "R28") (pin "1") (pinfunction "1_1") (pintype "passive"))
    )
  )
)
